# EnvironmentMonitorV6_1.net
KiCad netlist of a schematic drawn in EAGLE
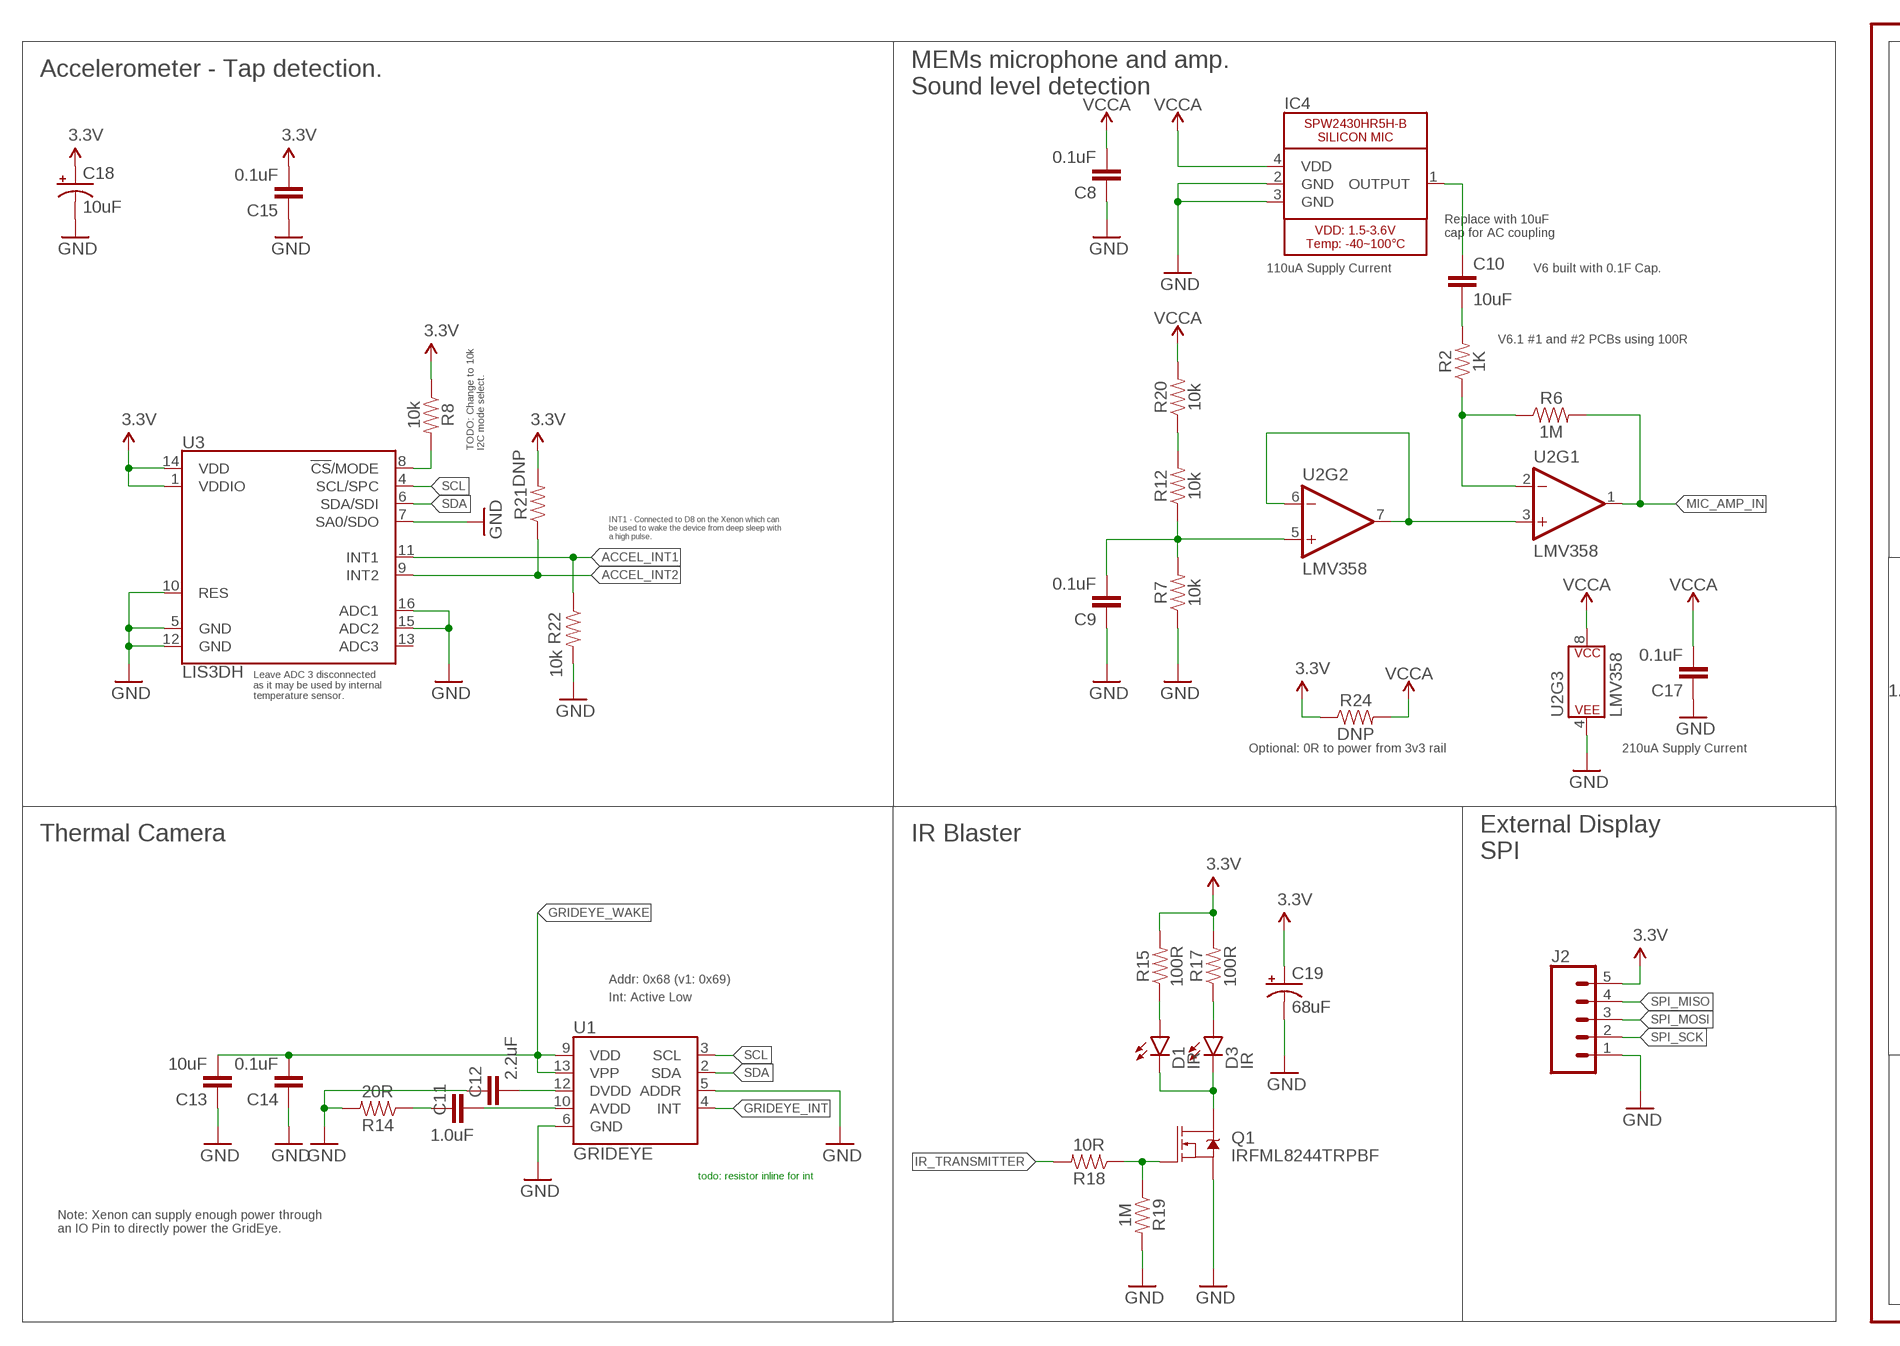
[diagram p0: schematic, sheet 1, part 1 of 2]
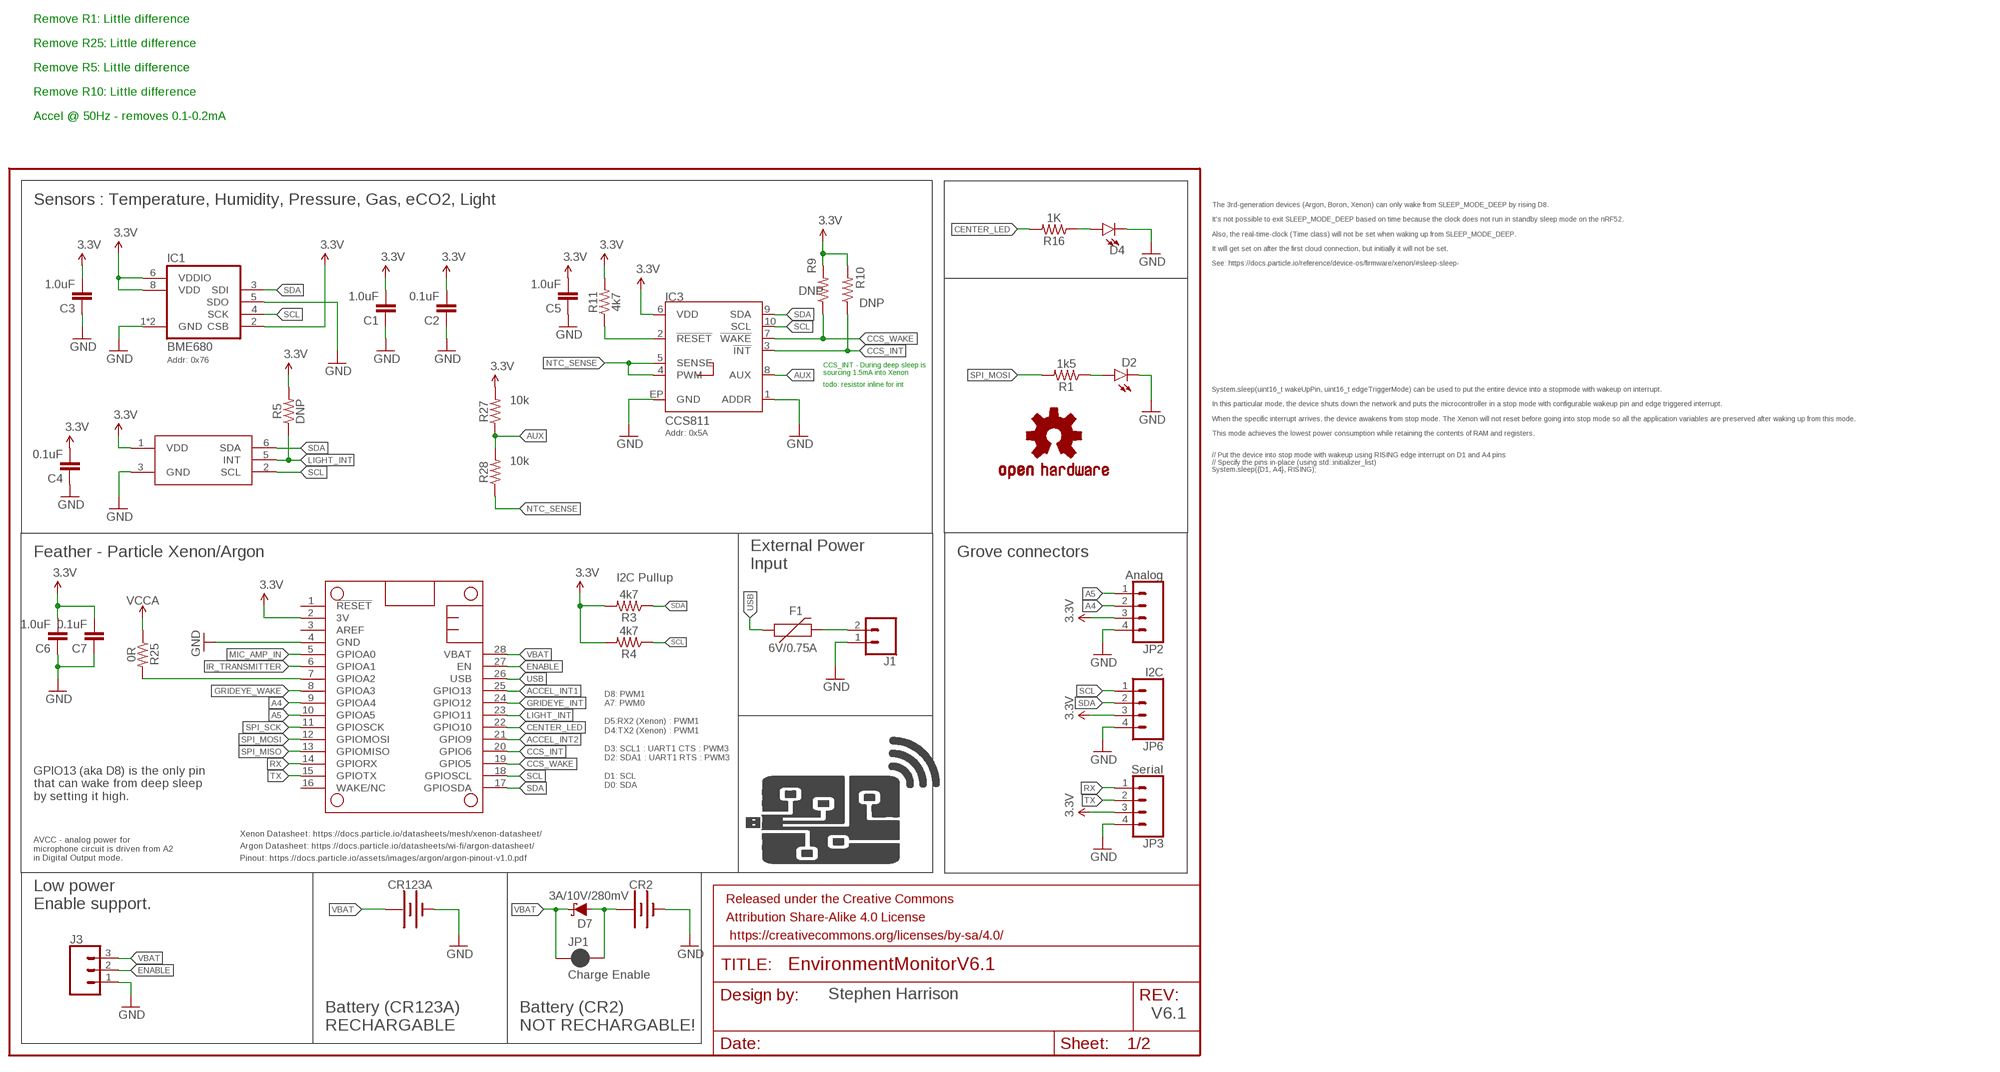
[diagram p1: schematic, sheet 1, part 2 of 2]
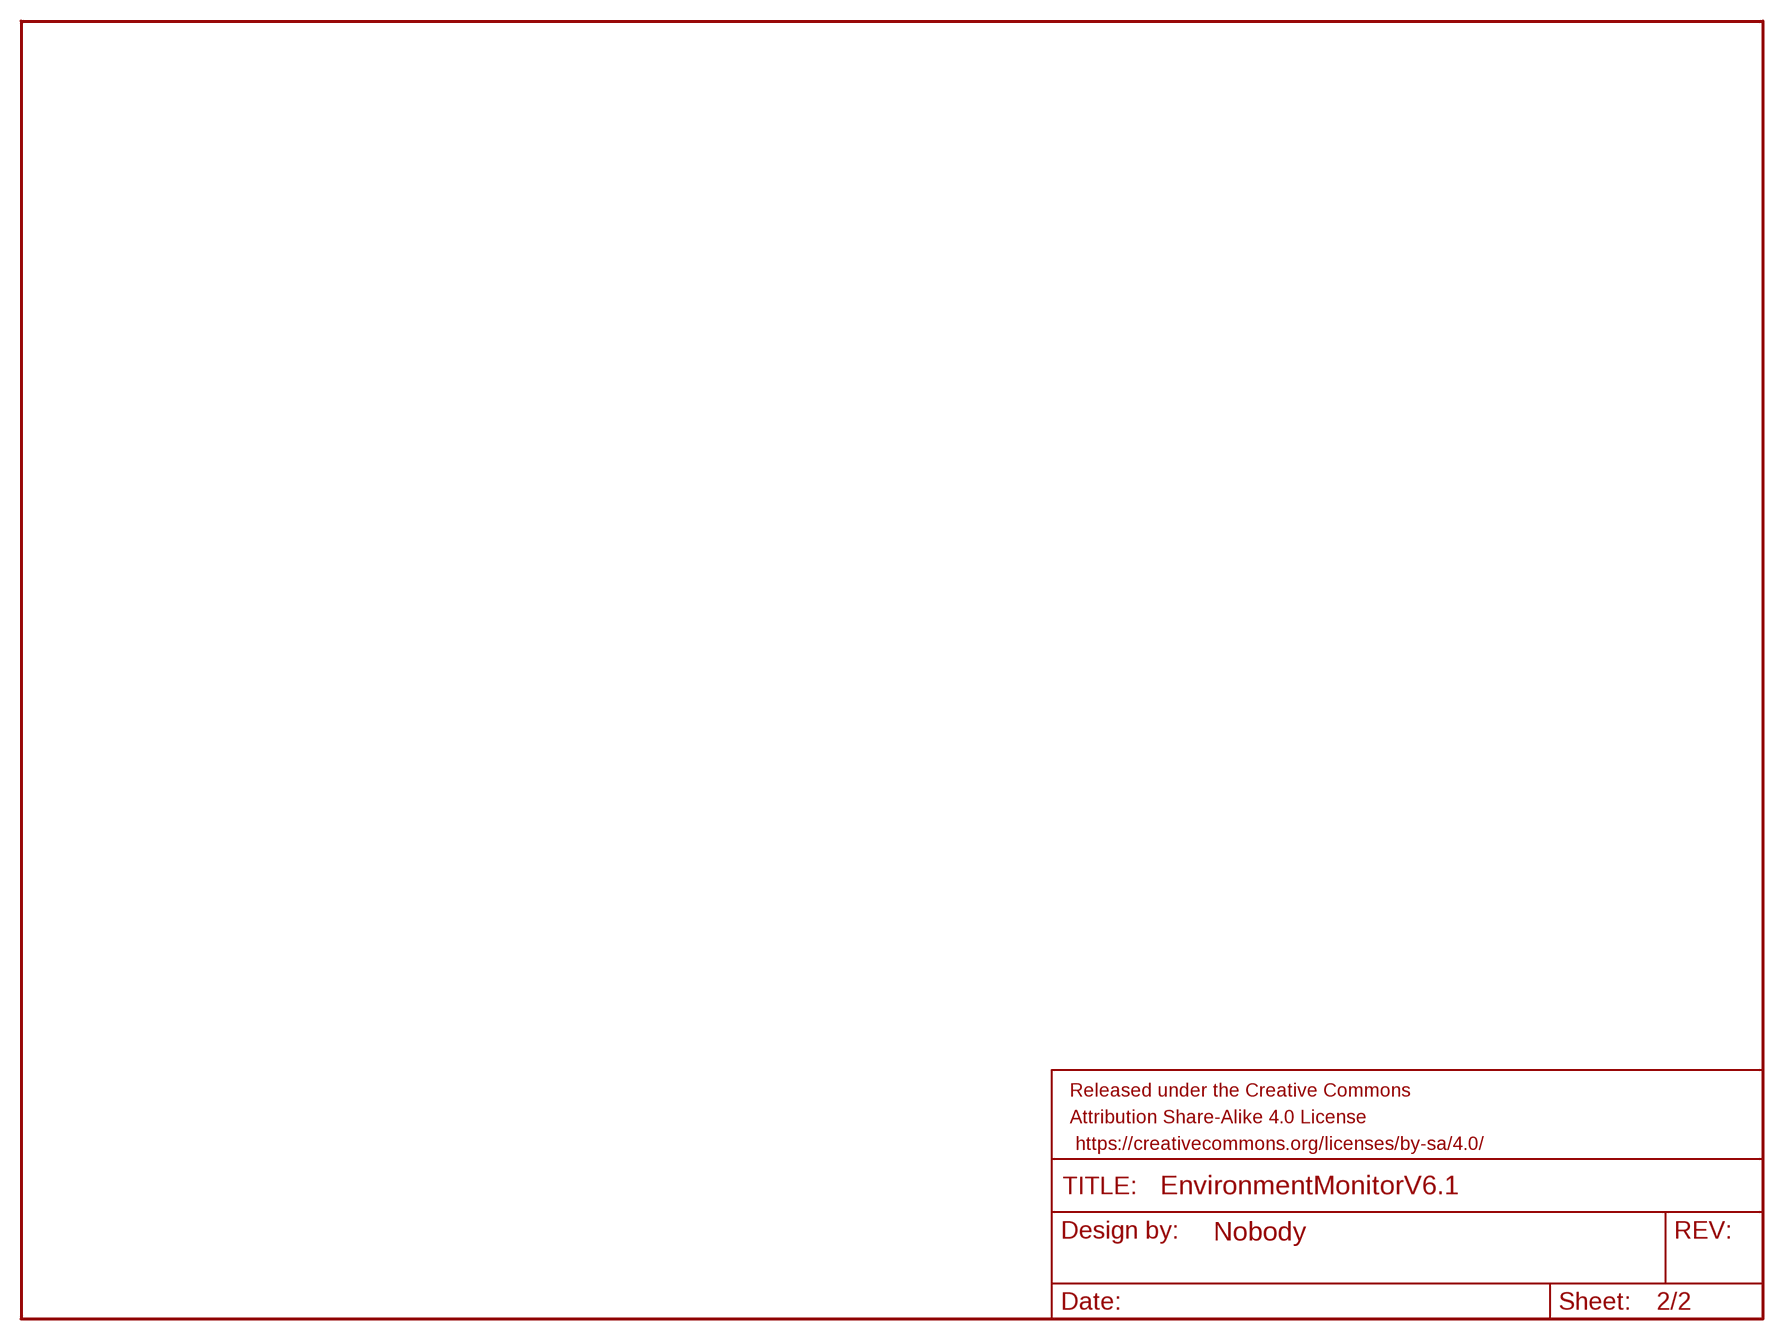
[diagram p2: schematic, sheet 2]

(export (version "E")
  (design (tool "Eeschema 10.0.6"))
  (components
    (comp (ref "FRAME2")
      (value "FRAME-LETTERNO_PACKAGE")
      (footprint "eagle-import:DUMMY")
      (fields (field (name "DESIGNER") "Nobody"))
      (libsource (lib "eagle-import") (part "FRAME-LETTERNO_PACKAGE"))
    )
    (comp (ref "C1")
      (value "1.0uF")
      (footprint "eagle-import:0805-CAP")
      (libsource (lib "eagle-import") (part "1.0UF-25V-+80/-20(0805){dblquote}"))
    )
    (comp (ref "C2")
      (value "0.1uF")
      (footprint "eagle-import:0805-CAP")
      (libsource (lib "eagle-import") (part "1.0UF-25V-+80/-20(0805){dblquote}"))
    )
    (comp (ref "C3")
      (value "1.0uF")
      (footprint "eagle-import:0805-CAP")
      (libsource (lib "eagle-import") (part "1.0UF-25V-+80/-20(0805){dblquote}"))
    )
    (comp (ref "C4")
      (value "0.1uF")
      (footprint "eagle-import:0805-CAP")
      (libsource (lib "eagle-import") (part "1.0UF-25V-+80/-20(0805){dblquote}"))
    )
    (comp (ref "C5")
      (value "1.0uF")
      (footprint "eagle-import:0805-CAP")
      (libsource (lib "eagle-import") (part "1.0UF-25V-+80/-20(0805){dblquote}"))
    )
    (comp (ref "C6")
      (value "1.0uF")
      (footprint "eagle-import:0805-CAP")
      (libsource (lib "eagle-import") (part "1.0UF-25V-+80/-20(0805){dblquote}"))
    )
    (comp (ref "C7")
      (value "0.1uF")
      (footprint "eagle-import:0805-CAP")
      (libsource (lib "eagle-import") (part "1.0UF-25V-+80/-20(0805){dblquote}"))
    )
    (comp (ref "C8")
      (value "0.1uF")
      (footprint "eagle-import:0805-CAP")
      (libsource (lib "eagle-import") (part "1.0UF-25V-+80/-20(0805){dblquote}"))
    )
    (comp (ref "C9")
      (value "0.1uF")
      (footprint "eagle-import:0805-CAP")
      (libsource (lib "eagle-import") (part "1.0UF-25V-+80/-20(0805){dblquote}"))
    )
    (comp (ref "C10")
      (value "10uF")
      (footprint "eagle-import:0805-CAP")
      (libsource (lib "eagle-import") (part "1.0UF-25V-+80/-20(0805){dblquote}"))
    )
    (comp (ref "C11")
      (value "1.0uF")
      (footprint "eagle-import:0805-CAP")
      (libsource (lib "eagle-import") (part "1.0UF-25V-+80/-20(0805){dblquote}"))
    )
    (comp (ref "C12")
      (value "2.2uF")
      (footprint "eagle-import:0805-CAP")
      (libsource (lib "eagle-import") (part "1.0UF-25V-+80/-20(0805){dblquote}"))
    )
    (comp (ref "C13")
      (value "10uF")
      (footprint "eagle-import:0805-CAP")
      (libsource (lib "eagle-import") (part "1.0UF-25V-+80/-20(0805){dblquote}"))
    )
    (comp (ref "C14")
      (value "0.1uF")
      (footprint "eagle-import:0805-CAP")
      (libsource (lib "eagle-import") (part "1.0UF-25V-+80/-20(0805){dblquote}"))
    )
    (comp (ref "C15")
      (value "0.1uF")
      (footprint "eagle-import:0805-CAP")
      (libsource (lib "eagle-import") (part "1.0UF-25V-+80/-20(0805){dblquote}"))
    )
    (comp (ref "C17")
      (value "0.1uF")
      (footprint "eagle-import:0805-CAP")
      (libsource (lib "eagle-import") (part "1.0UF-25V-+80/-20(0805){dblquote}"))
    )
    (comp (ref "C18")
      (value "10uF")
      (footprint "eagle-import:EIA3216")
      (fields (field (name "MFG") "T491A106K010AT"))
      (libsource (lib "eagle-import") (part "10UF-POLAR-EIA3216-16V-10%(TANT)"))
    )
    (comp (ref "C19")
      (value "68uF")
      (footprint "eagle-import:EIA3528")
      (libsource (lib "eagle-import") (part "68UF-POLAR-EIA3528-10V-10%(TANT)"))
    )
    (comp (ref "CR2")
      (value "BATTERYCR2-NO-HOLES")
      (footprint "eagle-import:BATTERY_CR2-HOLDER-NO-HOLES")
      (libsource (lib "eagle-import") (part "BATTERYCR2-NO-HOLES"))
    )
    (comp (ref "CR123A")
      (value "BATTERY-16340")
      (footprint "eagle-import:BATTERY_16340-HOLDER")
      (libsource (lib "eagle-import") (part "BATTERY-16340"))
    )
    (comp (ref "D1")
      (value "IR")
      (footprint "eagle-import:LED-1206")
      (libsource (lib "eagle-import") (part "LED1206"))
    )
    (comp (ref "D2")
      (value "LED1206-BOTTOM")
      (footprint "eagle-import:LED-1206-BOTTOM")
      (libsource (lib "eagle-import") (part "LED1206-BOTTOM"))
    )
    (comp (ref "D3")
      (value "IR")
      (footprint "eagle-import:LED-1206")
      (libsource (lib "eagle-import") (part "LED1206"))
    )
    (comp (ref "D4")
      (value "LED1206")
      (footprint "eagle-import:LED-1206")
      (libsource (lib "eagle-import") (part "ThingySticks_LED1206"))
    )
    (comp (ref "D7")
      (value "3A/10V/280mV")
      (footprint "eagle-import:SOD-323")
      (libsource (lib "eagle-import") (part "DIODE-SCHOTTKY-BAT60A"))
    )
    (comp (ref "F1")
      (value "6V/0.75A")
      (footprint "eagle-import:1206")
      (libsource (lib "eagle-import") (part "PPTC_THREE-QUARTER-AMP"))
    )
    (comp (ref "FRAME1")
      (value "FRAME-LETTER")
      (footprint "eagle-import:CREATIVE_COMMONS")
      (libsource (lib "eagle-import") (part "FRAME-LETTER"))
    )
    (comp (ref "IC1")
      (value "BME680")
      (footprint "eagle-import:BME680")
      (libsource (lib "eagle-import") (part "BME680"))
    )
    (comp (ref "IC2")
      (value "TCS3472")
      (footprint "eagle-import:FN-6")
      (libsource (lib "eagle-import") (part "TCS3472"))
    )
    (comp (ref "IC3")
      (value "CCS811")
      (footprint "eagle-import:LGA10")
      (libsource (lib "eagle-import") (part "CCS811"))
    )
    (comp (ref "IC4")
      (value "SPW2430HR5H-B")
      (footprint "eagle-import:SPW2430HR5H-B")
      (libsource (lib "eagle-import") (part "SPW2430HR5H-B"))
    )
    (comp (ref "IC5")
      (value "FEATHERWINGPADS_AND_PLACE_ONLY")
      (footprint "eagle-import:FEATHERWIND_PADS_AND_PLACE")
      (libsource (lib "eagle-import") (part "FEATHERWINGPADS_AND_PLACE_ONLY"))
    )
    (comp (ref "J1")
      (value "CONN_02JST-2-PH-SIDE")
      (footprint "eagle-import:JST-2-SMD")
      (libsource (lib "eagle-import") (part "CONN_02JST-2-PH-SIDE"))
    )
    (comp (ref "J2")
      (value "CONN_05SMD2")
      (footprint "eagle-import:1X05_1MM_RA")
      (libsource (lib "eagle-import") (part "CONN_05SMD2"))
    )
    (comp (ref "J3")
      (value "CONN_03SMD")
      (footprint "eagle-import:1X03-1MM-RA")
      (libsource (lib "eagle-import") (part "CONN_03SMD"))
    )
    (comp (ref "JP1")
      (value "Charge Enable")
      (footprint "eagle-import:SMT-JUMPER_2_NC_PASTE_SILK")
      (libsource (lib "eagle-import") (part "JUMPER-SMT_2_NC_PASTE_SILK"))
    )
    (comp (ref "JP2")
      (value "Analog")
      (footprint "eagle-import:JST-4-PH-GROVE")
      (libsource (lib "eagle-import") (part "CONN_04GROVE-JST-PH-4-2MM"))
    )
    (comp (ref "JP3")
      (value "Serial")
      (footprint "eagle-import:JST-4-PH-GROVE")
      (libsource (lib "eagle-import") (part "CONN_04GROVE-JST-PH-4-2MM"))
    )
    (comp (ref "JP6")
      (value "I2C")
      (footprint "eagle-import:JST-4-PH-GROVE")
      (libsource (lib "eagle-import") (part "CONN_04GROVE-JST-PH-4-2MM"))
    )
    (comp (ref "LOGO1")
      (value "OSHW-LOGOM")
      (footprint "eagle-import:OSHW-LOGO-M")
      (libsource (lib "eagle-import") (part "OSHW-LOGOM"))
    )
    (comp (ref "Q1")
      (value "IRFML8244TRPBF")
      (footprint "eagle-import:SOT23-3")
      (libsource (lib "eagle-import") (part "MOSFET-NCH-BSS138"))
    )
    (comp (ref "R1")
      (value "1k5")
      (footprint "eagle-import:0805")
      (libsource (lib "eagle-import") (part "RESISTOR0805"))
    )
    (comp (ref "R2")
      (value "1K")
      (footprint "eagle-import:0805")
      (libsource (lib "eagle-import") (part "RESISTOR0805"))
    )
    (comp (ref "R3")
      (value "4k7")
      (footprint "eagle-import:0805")
      (libsource (lib "eagle-import") (part "RESISTOR0805"))
    )
    (comp (ref "R4")
      (value "4k7")
      (footprint "eagle-import:0805")
      (libsource (lib "eagle-import") (part "RESISTOR0805"))
    )
    (comp (ref "R5")
      (value "DNP")
      (footprint "eagle-import:0805")
      (libsource (lib "eagle-import") (part "RESISTOR0805"))
    )
    (comp (ref "R6")
      (value "1M")
      (footprint "eagle-import:0805")
      (libsource (lib "eagle-import") (part "RESISTOR0805"))
    )
    (comp (ref "R7")
      (value "10k")
      (footprint "eagle-import:0805")
      (libsource (lib "eagle-import") (part "RESISTOR0805"))
    )
    (comp (ref "R8")
      (value "10k")
      (footprint "eagle-import:0805")
      (libsource (lib "eagle-import") (part "RESISTOR0805"))
    )
    (comp (ref "R9")
      (value "DNP")
      (footprint "eagle-import:0805")
      (libsource (lib "eagle-import") (part "RESISTOR0805"))
    )
    (comp (ref "R10")
      (value "DNP")
      (footprint "eagle-import:0805")
      (libsource (lib "eagle-import") (part "RESISTOR0805"))
    )
    (comp (ref "R11")
      (value "4k7")
      (footprint "eagle-import:0805")
      (libsource (lib "eagle-import") (part "RESISTOR0805"))
    )
    (comp (ref "R12")
      (value "10k")
      (footprint "eagle-import:0805")
      (libsource (lib "eagle-import") (part "RESISTOR0805"))
    )
    (comp (ref "R14")
      (value "20R")
      (footprint "eagle-import:0805")
      (libsource (lib "eagle-import") (part "RESISTOR0805"))
    )
    (comp (ref "R15")
      (value "100R")
      (footprint "eagle-import:0805")
      (libsource (lib "eagle-import") (part "RESISTOR0805"))
    )
    (comp (ref "R16")
      (value "1K")
      (footprint "eagle-import:0805")
      (libsource (lib "eagle-import") (part "RESISTOR0805"))
    )
    (comp (ref "R17")
      (value "100R")
      (footprint "eagle-import:0805")
      (libsource (lib "eagle-import") (part "RESISTOR0805"))
    )
    (comp (ref "R18")
      (value "10R")
      (footprint "eagle-import:0805")
      (libsource (lib "eagle-import") (part "RESISTOR0805"))
    )
    (comp (ref "R19")
      (value "1M")
      (footprint "eagle-import:0805")
      (libsource (lib "eagle-import") (part "RESISTOR0805"))
    )
    (comp (ref "R20")
      (value "10k")
      (footprint "eagle-import:0805")
      (libsource (lib "eagle-import") (part "RESISTOR0805"))
    )
    (comp (ref "R21")
      (value "DNP")
      (footprint "eagle-import:0805")
      (libsource (lib "eagle-import") (part "RESISTOR0805"))
    )
    (comp (ref "R22")
      (value "10k")
      (footprint "eagle-import:0805")
      (libsource (lib "eagle-import") (part "RESISTOR0805"))
    )
    (comp (ref "R24")
      (value "DNP")
      (footprint "eagle-import:0805")
      (libsource (lib "eagle-import") (part "RESISTOR0805"))
    )
    (comp (ref "R25")
      (value "0R")
      (footprint "eagle-import:0805")
      (libsource (lib "eagle-import") (part "RESISTOR0805"))
    )
    (comp (ref "R27")
      (value "10k")
      (footprint "eagle-import:0805")
      (libsource (lib "eagle-import") (part "RESISTOR0805"))
    )
    (comp (ref "R28")
      (value "10k")
      (footprint "eagle-import:0805")
      (libsource (lib "eagle-import") (part "RESISTOR0805"))
    )
    (comp (ref "U$1")
      (value "THINGYSTICKS_LOGOLOGO_2")
      (footprint "eagle-import:THINGYSTICKS_LOGO_2")
      (libsource (lib "eagle-import") (part "THINGYSTICKS_LOGOLOGO_2"))
    )
    (comp (ref "U1")
      (value "GRIDEYE")
      (footprint "eagle-import:GRIDEYE-AMG88")
      (libsource (lib "eagle-import") (part "GRIDEYE"))
    )
    (comp (ref "U2")
      (value "LMV358")
      (footprint "eagle-import:SO08")
      (libsource (lib "eagle-import") (part "LMV358SOIC"))
    )
    (comp (ref "U3")
      (value "LIS3DH")
      (footprint "eagle-import:LGA-16-3X3")
      (libsource (lib "eagle-import") (part "LIS3DH"))
    )
  )
  (nets
    (net (code "1") (name "3.3V") (class "Default")
      (node (ref "C1") (pin "2") (pinfunction "2_2") (pintype "passive"))
      (node (ref "C15") (pin "2") (pinfunction "2_2") (pintype "passive"))
      (node (ref "C18") (pin "+") (pinfunction "+_+") (pintype "passive"))
      (node (ref "C19") (pin "A") (pinfunction "+_A") (pintype "passive"))
      (node (ref "C2") (pin "2") (pinfunction "2_2") (pintype "passive"))
      (node (ref "C3") (pin "2") (pinfunction "2_2") (pintype "passive"))
      (node (ref "C4") (pin "2") (pinfunction "2_2") (pintype "passive"))
      (node (ref "C5") (pin "2") (pinfunction "2_2") (pintype "passive"))
      (node (ref "C6") (pin "2") (pinfunction "2_2") (pintype "passive"))
      (node (ref "C7") (pin "2") (pinfunction "2_2") (pintype "passive"))
      (node (ref "IC1") (pin "2") (pinfunction "CSB_2") (pintype "input"))
      (node (ref "IC1") (pin "6") (pinfunction "VDDIO_6") (pintype "power_in"))
      (node (ref "IC1") (pin "8") (pinfunction "VDD_8") (pintype "power_in"))
      (node (ref "IC2") (pin "1") (pinfunction "VDD_1") (pintype "bidirectional"))
      (node (ref "IC3") (pin "6") (pinfunction "VDD_6") (pintype "bidirectional"))
      (node (ref "IC5") (pin "2") (pinfunction "3V_2") (pintype "power_in"))
      (node (ref "J2") (pin "5") (pinfunction "5_5") (pintype "passive"))
      (node (ref "JP2") (pin "3") (pinfunction "3_3") (pintype "passive"))
      (node (ref "JP3") (pin "3") (pinfunction "3_3") (pintype "passive"))
      (node (ref "JP6") (pin "3") (pinfunction "3_3") (pintype "passive"))
      (node (ref "R10") (pin "2") (pinfunction "2_2") (pintype "passive"))
      (node (ref "R11") (pin "2") (pinfunction "2_2") (pintype "passive"))
      (node (ref "R15") (pin "2") (pinfunction "2_2") (pintype "passive"))
      (node (ref "R17") (pin "2") (pinfunction "2_2") (pintype "passive"))
      (node (ref "R21") (pin "2") (pinfunction "2_2") (pintype "passive"))
      (node (ref "R24") (pin "1") (pinfunction "1_1") (pintype "passive"))
      (node (ref "R27") (pin "2") (pinfunction "2_2") (pintype "passive"))
      (node (ref "R3") (pin "2") (pinfunction "2_2") (pintype "passive"))
      (node (ref "R4") (pin "2") (pinfunction "2_2") (pintype "passive"))
      (node (ref "R5") (pin "2") (pinfunction "2_2") (pintype "passive"))
      (node (ref "R8") (pin "1") (pinfunction "1_1") (pintype "passive"))
      (node (ref "R9") (pin "2") (pinfunction "2_2") (pintype "passive"))
      (node (ref "U3") (pin "1") (pinfunction "VDDIO_1") (pintype "bidirectional"))
      (node (ref "U3") (pin "14") (pinfunction "VDD_14") (pintype "bidirectional"))
    )
    (net (code "2") (name "A4") (class "Default")
      (node (ref "IC5") (pin "9") (pinfunction "GPIOA4_9") (pintype "bidirectional"))
      (node (ref "JP2") (pin "2") (pinfunction "2_2") (pintype "passive"))
    )
    (net (code "3") (name "A5") (class "Default")
      (node (ref "IC5") (pin "10") (pinfunction "GPIOA5_10") (pintype "bidirectional"))
      (node (ref "JP2") (pin "1") (pinfunction "1_1") (pintype "passive"))
    )
    (net (code "4") (name "ACCEL_INT1") (class "Default")
      (node (ref "IC5") (pin "25") (pinfunction "GPIO13_25") (pintype "bidirectional"))
      (node (ref "R22") (pin "1") (pinfunction "1_1") (pintype "passive"))
      (node (ref "U3") (pin "11") (pinfunction "INT1_11") (pintype "bidirectional"))
    )
    (net (code "5") (name "ACCEL_INT2") (class "Default")
      (node (ref "IC5") (pin "21") (pinfunction "GPIO9_21") (pintype "bidirectional"))
      (node (ref "R21") (pin "1") (pinfunction "1_1") (pintype "passive"))
      (node (ref "U3") (pin "9") (pinfunction "INT2_9") (pintype "bidirectional"))
    )
    (net (code "6") (name "AUX") (class "Default")
      (node (ref "IC3") (pin "8") (pinfunction "AUX_8") (pintype "bidirectional"))
      (node (ref "R27") (pin "1") (pinfunction "1_1") (pintype "passive"))
      (node (ref "R28") (pin "2") (pinfunction "2_2") (pintype "passive"))
    )
    (net (code "7") (name "CCS_INT") (class "Default")
      (node (ref "IC3") (pin "3") (pinfunction "~{INT}_3") (pintype "bidirectional"))
      (node (ref "IC5") (pin "20") (pinfunction "GPIO6_20") (pintype "bidirectional"))
      (node (ref "R10") (pin "1") (pinfunction "1_1") (pintype "passive"))
    )
    (net (code "8") (name "CCS_WAKE") (class "Default")
      (node (ref "IC3") (pin "7") (pinfunction "~{WAKE}_7") (pintype "bidirectional"))
      (node (ref "IC5") (pin "19") (pinfunction "GPIO5_19") (pintype "bidirectional"))
      (node (ref "R9") (pin "1") (pinfunction "1_1") (pintype "passive"))
    )
    (net (code "9") (name "CENTER_LED") (class "Default")
      (node (ref "IC5") (pin "22") (pinfunction "GPIO10_22") (pintype "bidirectional"))
      (node (ref "R16") (pin "2") (pinfunction "2_2") (pintype "passive"))
    )
    (net (code "10") (name "ENABLE") (class "Default")
      (node (ref "IC5") (pin "27") (pinfunction "EN_27") (pintype "passive"))
      (node (ref "J3") (pin "2") (pinfunction "2_2") (pintype "passive"))
    )
    (net (code "11") (name "GND") (class "Default")
      (node (ref "C1") (pin "1") (pinfunction "1_1") (pintype "passive"))
      (node (ref "C12") (pin "1") (pinfunction "1_1") (pintype "passive"))
      (node (ref "C13") (pin "1") (pinfunction "1_1") (pintype "passive"))
      (node (ref "C14") (pin "1") (pinfunction "1_1") (pintype "passive"))
      (node (ref "C15") (pin "1") (pinfunction "1_1") (pintype "passive"))
      (node (ref "C17") (pin "1") (pinfunction "1_1") (pintype "passive"))
      (node (ref "C18") (pin "-") (pinfunction "-_-") (pintype "passive"))
      (node (ref "C19") (pin "C") (pinfunction "-_C") (pintype "passive"))
      (node (ref "C2") (pin "1") (pinfunction "1_1") (pintype "passive"))
      (node (ref "C3") (pin "1") (pinfunction "1_1") (pintype "passive"))
      (node (ref "C4") (pin "1") (pinfunction "1_1") (pintype "passive"))
      (node (ref "C5") (pin "1") (pinfunction "1_1") (pintype "passive"))
      (node (ref "C6") (pin "1") (pinfunction "1_1") (pintype "passive"))
      (node (ref "C7") (pin "1") (pinfunction "1_1") (pintype "passive"))
      (node (ref "C8") (pin "1") (pinfunction "1_1") (pintype "passive"))
      (node (ref "C9") (pin "1") (pinfunction "1_1") (pintype "passive"))
      (node (ref "CR123A") (pin "P$2") (pinfunction "-_P$2") (pintype "power_in"))
      (node (ref "CR2") (pin "P$2") (pinfunction "-_P$2") (pintype "power_in"))
      (node (ref "D2") (pin "C") (pinfunction "C_C") (pintype "passive"))
      (node (ref "D4") (pin "C") (pinfunction "C_C") (pintype "passive"))
      (node (ref "IC1") (pin "1") (pinfunction "GND_1") (pintype "power_in"))
      (node (ref "IC1") (pin "5") (pinfunction "SDO_5") (pintype "output"))
      (node (ref "IC1") (pin "7") (pinfunction "GND_7") (pintype "power_in"))
      (node (ref "IC2") (pin "3") (pinfunction "GND_3") (pintype "bidirectional"))
      (node (ref "IC3") (pin "1") (pinfunction "ADDR_1") (pintype "bidirectional"))
      (node (ref "IC3") (pin "EP") (pinfunction "GND_EP") (pintype "bidirectional"))
      (node (ref "IC4") (pin "2") (pinfunction "GND_2") (pintype "power_in"))
      (node (ref "IC4") (pin "3") (pinfunction "GND_3") (pintype "power_in"))
      (node (ref "IC5") (pin "4") (pinfunction "GND_4") (pintype "power_in"))
      (node (ref "J1") (pin "1") (pinfunction "2_1") (pintype "passive"))
      (node (ref "J2") (pin "1") (pinfunction "1_1") (pintype "passive"))
      (node (ref "J3") (pin "1") (pinfunction "1_1") (pintype "passive"))
      (node (ref "JP2") (pin "4") (pinfunction "4_4") (pintype "passive"))
      (node (ref "JP3") (pin "4") (pinfunction "4_4") (pintype "passive"))
      (node (ref "JP6") (pin "4") (pinfunction "4_4") (pintype "passive"))
      (node (ref "Q1") (pin "2") (pinfunction "S_2") (pintype "bidirectional"))
      (node (ref "R14") (pin "2") (pinfunction "2_2") (pintype "passive"))
      (node (ref "R19") (pin "2") (pinfunction "2_2") (pintype "passive"))
      (node (ref "R22") (pin "2") (pinfunction "2_2") (pintype "passive"))
      (node (ref "R7") (pin "1") (pinfunction "1_1") (pintype "passive"))
      (node (ref "U1") (pin "5") (pinfunction "ADDR_5") (pintype "bidirectional"))
      (node (ref "U1") (pin "6") (pinfunction "GND_6") (pintype "bidirectional"))
      (node (ref "U2") (pin "4") (pinfunction "P$V-_4") (pintype "bidirectional"))
      (node (ref "U3") (pin "10") (pinfunction "RES_10") (pintype "bidirectional"))
      (node (ref "U3") (pin "12") (pinfunction "GND_12") (pintype "bidirectional"))
      (node (ref "U3") (pin "15") (pinfunction "ADC2_15") (pintype "bidirectional"))
      (node (ref "U3") (pin "16") (pinfunction "ADC1_16") (pintype "bidirectional"))
      (node (ref "U3") (pin "5") (pinfunction "GND_5") (pintype "bidirectional"))
      (node (ref "U3") (pin "7") (pinfunction "SA0/SDO_7") (pintype "bidirectional"))
    )
    (net (code "12") (name "GRIDEYE_INT") (class "Default")
      (node (ref "IC5") (pin "24") (pinfunction "GPIO12_24") (pintype "bidirectional"))
      (node (ref "U1") (pin "4") (pinfunction "INT_4") (pintype "bidirectional"))
    )
    (net (code "13") (name "GRIDEYE_WAKE") (class "Default")
      (node (ref "C13") (pin "2") (pinfunction "2_2") (pintype "passive"))
      (node (ref "C14") (pin "2") (pinfunction "2_2") (pintype "passive"))
      (node (ref "IC5") (pin "8") (pinfunction "GPIOA3_8") (pintype "bidirectional"))
      (node (ref "U1") (pin "13") (pinfunction "VPP_13") (pintype "bidirectional"))
      (node (ref "U1") (pin "9") (pinfunction "VDD_9") (pintype "bidirectional"))
    )
    (net (code "14") (name "IR_TRANSMITTER") (class "Default")
      (node (ref "IC5") (pin "6") (pinfunction "GPIOA1_6") (pintype "bidirectional"))
      (node (ref "R18") (pin "2") (pinfunction "2_2") (pintype "passive"))
    )
    (net (code "15") (name "LIGHT_INT") (class "Default")
      (node (ref "IC2") (pin "5") (pinfunction "INT_5") (pintype "bidirectional"))
      (node (ref "IC5") (pin "23") (pinfunction "GPIO11_23") (pintype "bidirectional"))
      (node (ref "R5") (pin "1") (pinfunction "1_1") (pintype "passive"))
    )
    (net (code "16") (name "MIC_AMP_IN") (class "Default")
      (node (ref "IC5") (pin "5") (pinfunction "GPIOA0_5") (pintype "bidirectional"))
      (node (ref "R6") (pin "2") (pinfunction "2_2") (pintype "passive"))
      (node (ref "U2") (pin "1") (pinfunction "OUT_1") (pintype "output"))
    )
    (net (code "17") (name "NTC_SENSE") (class "Default")
      (node (ref "IC3") (pin "4") (pinfunction "PWM_4") (pintype "bidirectional"))
      (node (ref "IC3") (pin "5") (pinfunction "SENSE_5") (pintype "bidirectional"))
      (node (ref "R28") (pin "1") (pinfunction "1_1") (pintype "passive"))
    )
    (net (code "18") (name "Net-(C10-Pad2)") (class "Default")
      (node (ref "C10") (pin "2") (pinfunction "2_2") (pintype "passive"))
      (node (ref "R2") (pin "2") (pinfunction "2_2") (pintype "passive"))
    )
    (net (code "19") (name "Net-(C11-Pad1)") (class "Default")
      (node (ref "C11") (pin "1") (pinfunction "1_1") (pintype "passive"))
      (node (ref "R14") (pin "1") (pinfunction "1_1") (pintype "passive"))
    )
    (net (code "20") (name "Net-(CR2-+)") (class "Default")
      (node (ref "CR2") (pin "P$1") (pinfunction "+_P$1") (pintype "power_in"))
      (node (ref "D7") (pin "A") (pinfunction "A_A") (pintype "passive"))
      (node (ref "JP1") (pin "2") (pinfunction "2_2") (pintype "passive"))
    )
    (net (code "21") (name "Net-(D1-PadA)") (class "Default")
      (node (ref "D1") (pin "A") (pinfunction "A_A") (pintype "passive"))
      (node (ref "R15") (pin "1") (pinfunction "1_1") (pintype "passive"))
    )
    (net (code "22") (name "Net-(D2-PadA)") (class "Default")
      (node (ref "D2") (pin "A") (pinfunction "A_A") (pintype "passive"))
      (node (ref "R1") (pin "1") (pinfunction "1_1") (pintype "passive"))
    )
    (net (code "23") (name "Net-(D3-PadA)") (class "Default")
      (node (ref "D3") (pin "A") (pinfunction "A_A") (pintype "passive"))
      (node (ref "R17") (pin "1") (pinfunction "1_1") (pintype "passive"))
    )
    (net (code "24") (name "Net-(D4-PadA)") (class "Default")
      (node (ref "D4") (pin "A") (pinfunction "A_A") (pintype "passive"))
      (node (ref "R16") (pin "1") (pinfunction "1_1") (pintype "passive"))
    )
    (net (code "25") (name "Net-(IC3-~{RESET})") (class "Default")
      (node (ref "IC3") (pin "2") (pinfunction "~{RESET}_2") (pintype "bidirectional"))
      (node (ref "R11") (pin "1") (pinfunction "1_1") (pintype "passive"))
    )
    (net (code "26") (name "Net-(IC4-OUTPUT)") (class "Default")
      (node (ref "C10") (pin "1") (pinfunction "1_1") (pintype "passive"))
      (node (ref "IC4") (pin "1") (pinfunction "OUTPUT_1") (pintype "output"))
    )
    (net (code "27") (name "Net-(IC5-GPIOA2)") (class "Default")
      (node (ref "IC5") (pin "7") (pinfunction "GPIOA2_7") (pintype "bidirectional"))
      (node (ref "R25") (pin "2") (pinfunction "2_2") (pintype "passive"))
    )
    (net (code "28") (name "Net-(J1-1)") (class "Default")
      (node (ref "F1") (pin "2") (pinfunction "2_2") (pintype "bidirectional"))
      (node (ref "J1") (pin "2") (pinfunction "1_2") (pintype "passive"))
    )
    (net (code "29") (name "Net-(Q1-D)") (class "Default")
      (node (ref "D1") (pin "C") (pinfunction "C_C") (pintype "passive"))
      (node (ref "D3") (pin "C") (pinfunction "C_C") (pintype "passive"))
      (node (ref "Q1") (pin "3") (pinfunction "D_3") (pintype "bidirectional"))
    )
    (net (code "30") (name "Net-(Q1-G)") (class "Default")
      (node (ref "Q1") (pin "1") (pinfunction "G_1") (pintype "bidirectional"))
      (node (ref "R18") (pin "1") (pinfunction "1_1") (pintype "passive"))
      (node (ref "R19") (pin "1") (pinfunction "1_1") (pintype "passive"))
    )
    (net (code "31") (name "Net-(R12-Pad2)") (class "Default")
      (node (ref "R12") (pin "2") (pinfunction "2_2") (pintype "passive"))
      (node (ref "R20") (pin "1") (pinfunction "1_1") (pintype "passive"))
    )
    (net (code "32") (name "Net-(U1-AVDD)") (class "Default")
      (node (ref "C11") (pin "2") (pinfunction "2_2") (pintype "passive"))
      (node (ref "U1") (pin "10") (pinfunction "AVDD_10") (pintype "bidirectional"))
    )
    (net (code "33") (name "Net-(U1-DVDD)") (class "Default")
      (node (ref "C12") (pin "2") (pinfunction "2_2") (pintype "passive"))
      (node (ref "U1") (pin "12") (pinfunction "DVDD_12") (pintype "bidirectional"))
    )
    (net (code "34") (name "Net-(U2A-+IN)") (class "Default")
      (node (ref "U2") (pin "3") (pinfunction "+IN_3") (pintype "input"))
      (node (ref "U2") (pin "6") (pinfunction "-IN_6") (pintype "input"))
      (node (ref "U2") (pin "7") (pinfunction "OUT_7") (pintype "output"))
    )
    (net (code "35") (name "Net-(U2A--IN)") (class "Default")
      (node (ref "R2") (pin "1") (pinfunction "1_1") (pintype "passive"))
      (node (ref "R6") (pin "1") (pinfunction "1_1") (pintype "passive"))
      (node (ref "U2") (pin "2") (pinfunction "-IN_2") (pintype "input"))
    )
    (net (code "36") (name "Net-(U2B-+IN)") (class "Default")
      (node (ref "C9") (pin "2") (pinfunction "2_2") (pintype "passive"))
      (node (ref "R12") (pin "1") (pinfunction "1_1") (pintype "passive"))
      (node (ref "R7") (pin "2") (pinfunction "2_2") (pintype "passive"))
      (node (ref "U2") (pin "5") (pinfunction "+IN_5") (pintype "input"))
    )
    (net (code "37") (name "Net-(U3-~{CS}{slash}MODE)") (class "Default")
      (node (ref "R8") (pin "2") (pinfunction "2_2") (pintype "passive"))
      (node (ref "U3") (pin "8") (pinfunction "~{CS}/MODE_8") (pintype "bidirectional"))
    )
    (net (code "38") (name "RX") (class "Default")
      (node (ref "IC5") (pin "14") (pinfunction "GPIORX_14") (pintype "bidirectional"))
      (node (ref "JP3") (pin "1") (pinfunction "1_1") (pintype "passive"))
    )
    (net (code "39") (name "SCL") (class "Default")
      (node (ref "IC1") (pin "4") (pinfunction "SCK_4") (pintype "input"))
      (node (ref "IC2") (pin "2") (pinfunction "SCL_2") (pintype "bidirectional"))
      (node (ref "IC3") (pin "10") (pinfunction "SCL_10") (pintype "bidirectional"))
      (node (ref "IC5") (pin "18") (pinfunction "GPIOSCL_18") (pintype "bidirectional"))
      (node (ref "JP6") (pin "1") (pinfunction "1_1") (pintype "passive"))
      (node (ref "R4") (pin "1") (pinfunction "1_1") (pintype "passive"))
      (node (ref "U1") (pin "3") (pinfunction "SCL_3") (pintype "bidirectional"))
      (node (ref "U3") (pin "4") (pinfunction "SCL/SPC_4") (pintype "bidirectional"))
    )
    (net (code "40") (name "SDA") (class "Default")
      (node (ref "IC1") (pin "3") (pinfunction "SDI_3") (pintype "input"))
      (node (ref "IC2") (pin "6") (pinfunction "SDA_6") (pintype "bidirectional"))
      (node (ref "IC3") (pin "9") (pinfunction "SDA_9") (pintype "bidirectional"))
      (node (ref "IC5") (pin "17") (pinfunction "GPIOSDA_17") (pintype "bidirectional"))
      (node (ref "JP6") (pin "2") (pinfunction "2_2") (pintype "passive"))
      (node (ref "R3") (pin "1") (pinfunction "1_1") (pintype "passive"))
      (node (ref "U1") (pin "2") (pinfunction "SDA_2") (pintype "bidirectional"))
      (node (ref "U3") (pin "6") (pinfunction "SDA/SDI_6") (pintype "bidirectional"))
    )
    (net (code "41") (name "SPI_MISO") (class "Default")
      (node (ref "IC5") (pin "13") (pinfunction "GPIOMISO_13") (pintype "bidirectional"))
      (node (ref "J2") (pin "4") (pinfunction "4_4") (pintype "passive"))
    )
    (net (code "42") (name "SPI_MOSI") (class "Default")
      (node (ref "IC5") (pin "12") (pinfunction "GPIOMOSI_12") (pintype "bidirectional"))
      (node (ref "J2") (pin "3") (pinfunction "3_3") (pintype "passive"))
      (node (ref "R1") (pin "2") (pinfunction "2_2") (pintype "passive"))
    )
    (net (code "43") (name "SPI_SCK") (class "Default")
      (node (ref "IC5") (pin "11") (pinfunction "GPIOSCK_11") (pintype "bidirectional"))
      (node (ref "J2") (pin "2") (pinfunction "2_2") (pintype "passive"))
    )
    (net (code "44") (name "TX") (class "Default")
      (node (ref "IC5") (pin "15") (pinfunction "GPIOTX_15") (pintype "bidirectional"))
      (node (ref "JP3") (pin "2") (pinfunction "2_2") (pintype "passive"))
    )
    (net (code "45") (name "USB") (class "Default")
      (node (ref "F1") (pin "1") (pinfunction "1_1") (pintype "bidirectional"))
      (node (ref "IC5") (pin "26") (pinfunction "USB_26") (pintype "power_in"))
    )
    (net (code "46") (name "VBAT") (class "Default")
      (node (ref "CR123A") (pin "P$1") (pinfunction "+_P$1") (pintype "power_in"))
      (node (ref "D7") (pin "C") (pinfunction "C_C") (pintype "passive"))
      (node (ref "IC5") (pin "28") (pinfunction "VBAT_28") (pintype "power_in"))
      (node (ref "J3") (pin "3") (pinfunction "3_3") (pintype "passive"))
      (node (ref "JP1") (pin "1") (pinfunction "1_1") (pintype "passive"))
    )
    (net (code "47") (name "VCCA") (class "Default")
      (node (ref "C17") (pin "2") (pinfunction "2_2") (pintype "passive"))
      (node (ref "C8") (pin "2") (pinfunction "2_2") (pintype "passive"))
      (node (ref "IC4") (pin "4") (pinfunction "VDD_4") (pintype "power_in"))
      (node (ref "R20") (pin "2") (pinfunction "2_2") (pintype "passive"))
      (node (ref "R24") (pin "2") (pinfunction "2_2") (pintype "passive"))
      (node (ref "R25") (pin "1") (pinfunction "1_1") (pintype "passive"))
      (node (ref "U2") (pin "8") (pinfunction "P$V+_8") (pintype "bidirectional"))
    )
    (net (code "48") (name "unconnected-(IC5-AREF-Pad3)") (class "Default")
      (node (ref "IC5") (pin "3") (pinfunction "AREF_3") (pintype "passive"))
    )
    (net (code "49") (name "unconnected-(IC5-WAKE{slash}NC-Pad16)") (class "Default")
      (node (ref "IC5") (pin "16") (pinfunction "WAKE/NC_16") (pintype "passive"))
    )
    (net (code "50") (name "unconnected-(IC5-~{RESET}-Pad1)") (class "Default")
      (node (ref "IC5") (pin "1") (pinfunction "~{RESET}_1") (pintype "input"))
    )
    (net (code "51") (name "unconnected-(U3-ADC3-Pad13)") (class "Default")
      (node (ref "U3") (pin "13") (pinfunction "ADC3_13") (pintype "bidirectional"))
    )
  )
)
